# MCPICKUP.net
KiCad netlist of a schematic drawn in EasyEDA
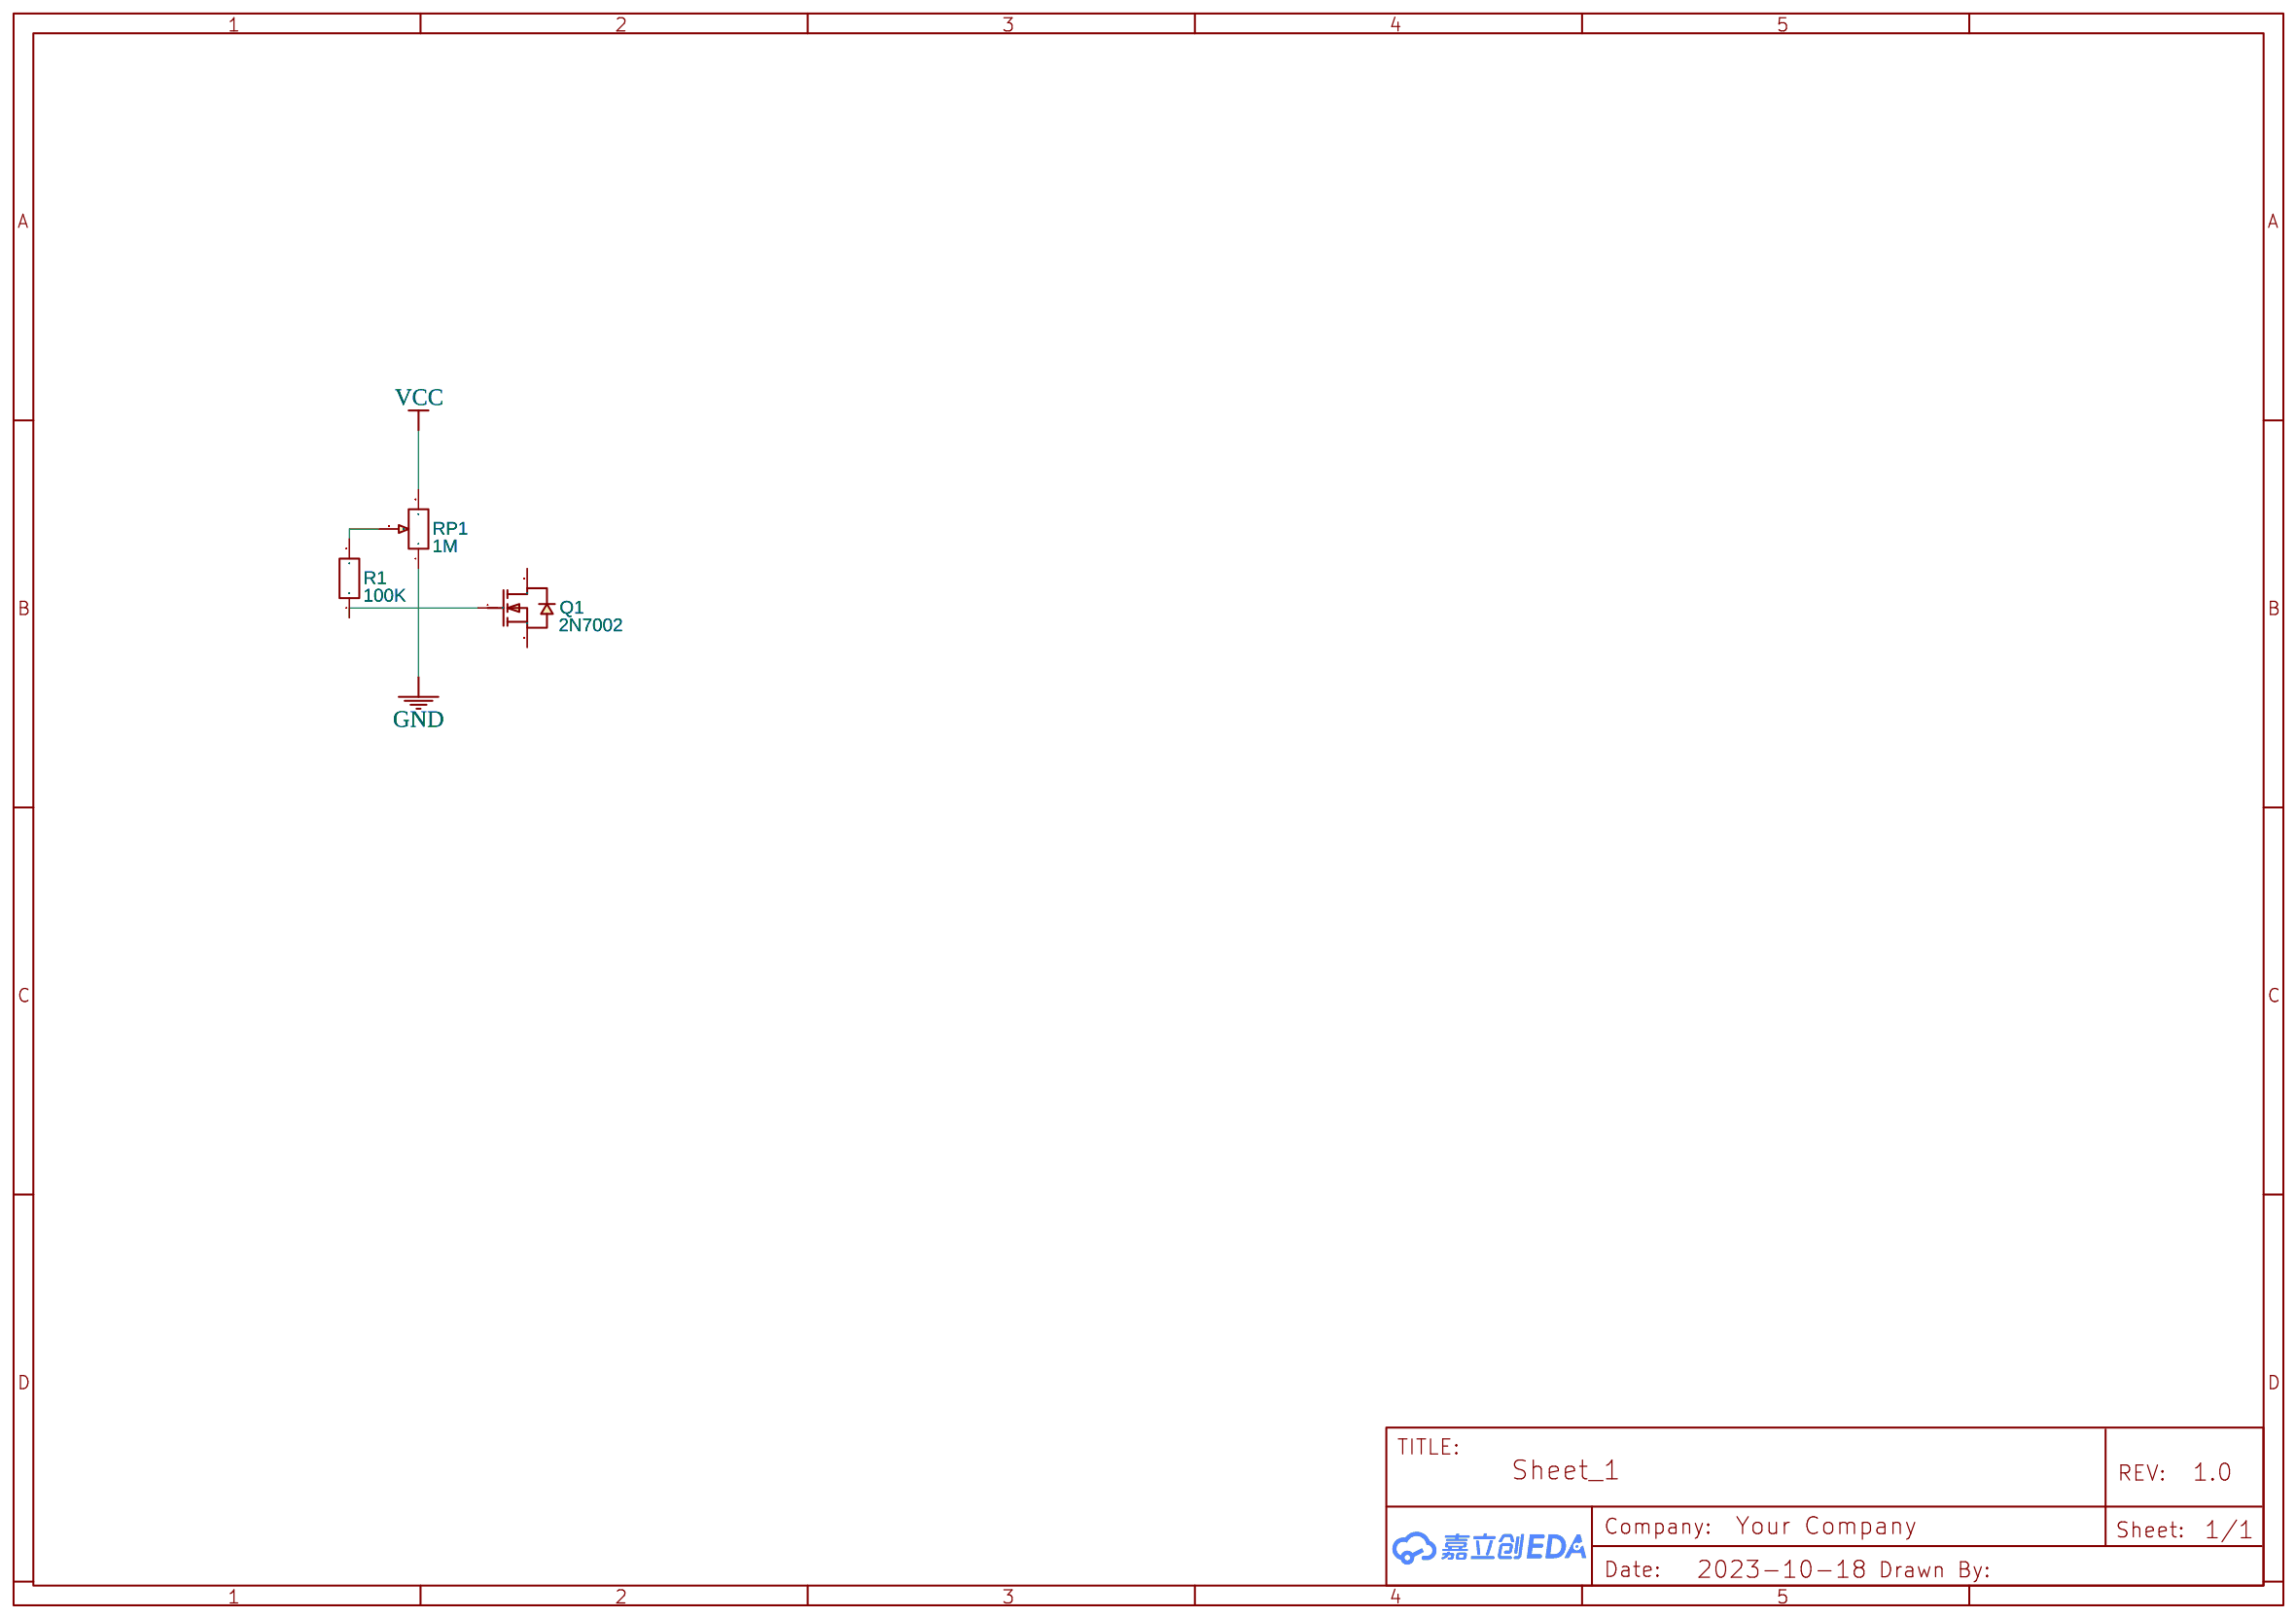
[diagram p0: schematic sheet]

(export (version "E")
  (design (tool "Eeschema 10.0.6"))
  (components
    (comp (ref "Q1")
      (value "2N7002")
      (fields (field (name "BOM_Manufacturer Part") "2N7002,215") (field (name "BOM_Supplier Part") "C65189"))
      (libsource (lib "") (part "2N7002"))
    )
    (comp (ref "R1") (value "100K") (libsource (lib "") (part "R_0603_EU")))
    (comp (ref "RP1") (value "1M") (libsource (lib "") (part "R_3296W_EU")))
  )
  (nets
    (net (code "1") (name "GND") (class "Default")
      (node (ref "RP1") (pin "1") (pinfunction "1_1") (pintype "input"))
    )
    (net (code "2") (name "Net-(Q1-G)") (class "Default")
      (node (ref "Q1") (pin "1") (pinfunction "G_1") (pintype "unspecified"))
      (node (ref "R1") (pin "1") (pinfunction "1_1") (pintype "unspecified"))
    )
    (net (code "3") (name "Net-(R1-Pad2)") (class "Default")
      (node (ref "R1") (pin "2") (pinfunction "2_2") (pintype "unspecified"))
      (node (ref "RP1") (pin "2") (pinfunction "2_2") (pintype "input"))
    )
    (net (code "4") (name "VCC") (class "Default")
      (node (ref "RP1") (pin "3") (pinfunction "3_3") (pintype "input"))
    )
    (net (code "5") (name "unconnected-(Q1-D-Pad3)") (class "Default")
      (node (ref "Q1") (pin "3") (pinfunction "D_3") (pintype "unspecified"))
    )
    (net (code "6") (name "unconnected-(Q1-S-Pad2)") (class "Default")
      (node (ref "Q1") (pin "2") (pinfunction "S_2") (pintype "unspecified"))
    )
  )
)
